# SNES_DRONE_PSU.net
KiCad netlist of a schematic drawn in Altium Designer
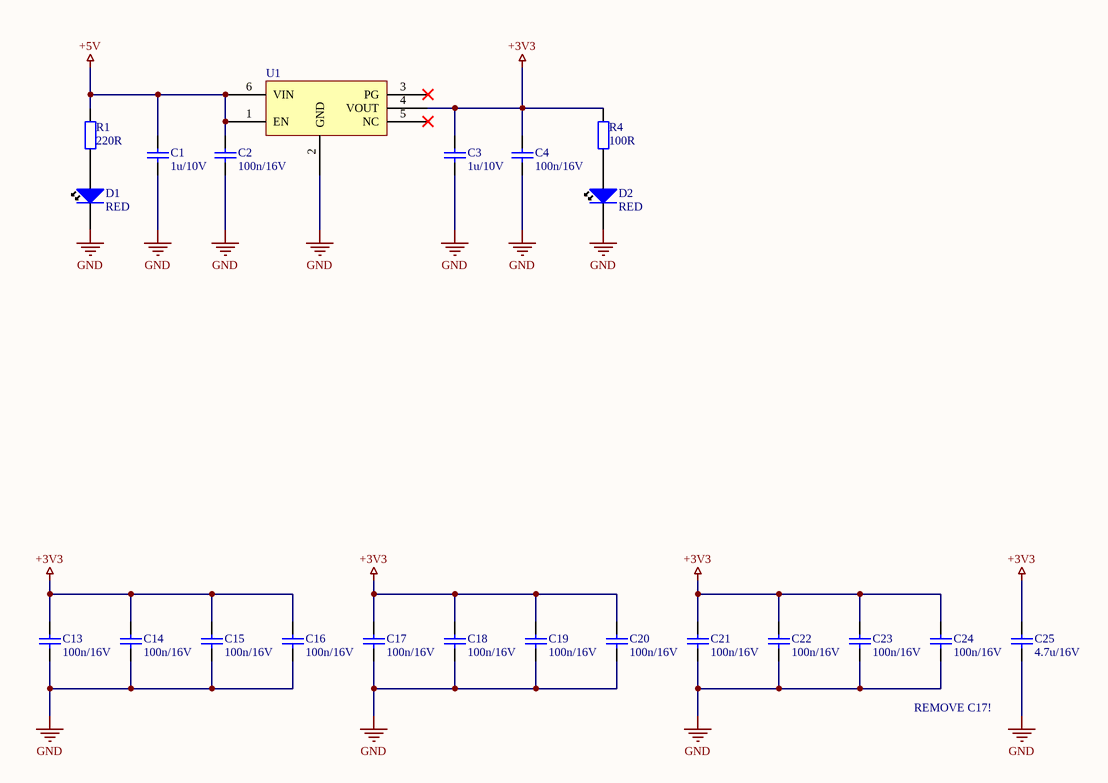
[diagram p0: SNES_DRONE_PSU.SchDoc]

(export (version "E")
  (design (tool "Eeschema 10.0.6"))
  (components
    (comp (ref "C1")
      (value "1u/10V")
      (footprint "0603_RES")
      (description "Keramikvielschichtkondensator, SMD, 1 µF, 10 V, 0603 [Metrisch 1608], ± 20%, X5R, WCAP-CSGP Series")
      (libsource (lib "My_Integrated_Library") (part "Cap_1u_0603"))
    )
    (comp (ref "C2")
      (value "100n/16V")
      (footprint "0402_RES")
      (description "Keramikvielschichtkondensator, SMD, 0.1 µF, 16 V, 0402 [Metrisch 1005], ± 10%, X5R, Baureihe MC")
      (libsource (lib "My_Integrated_Library") (part "Cap_100n_0402"))
    )
    (comp (ref "C3")
      (value "1u/10V")
      (footprint "0603_RES")
      (description "Keramikvielschichtkondensator, SMD, 1 µF, 10 V, 0603 [Metrisch 1608], ± 20%, X5R, WCAP-CSGP Series")
      (libsource (lib "My_Integrated_Library") (part "Cap_1u_0603"))
    )
    (comp (ref "C4")
      (value "100n/16V")
      (footprint "0402_RES")
      (description "Keramikvielschichtkondensator, SMD, 0.1 µF, 16 V, 0402 [Metrisch 1005], ± 10%, X5R, Baureihe MC")
      (libsource (lib "My_Integrated_Library") (part "Cap_100n_0402"))
    )
    (comp (ref "C13")
      (value "100n/16V")
      (footprint "0402_RES")
      (description "Keramikvielschichtkondensator, SMD, 0.1 µF, 16 V, 0402 [Metrisch 1005], ± 10%, X5R, Baureihe MC")
      (libsource (lib "My_Integrated_Library") (part "Cap_100n_0402"))
    )
    (comp (ref "C14")
      (value "100n/16V")
      (footprint "0402_RES")
      (description "Keramikvielschichtkondensator, SMD, 0.1 µF, 16 V, 0402 [Metrisch 1005], ± 10%, X5R, Baureihe MC")
      (libsource (lib "My_Integrated_Library") (part "Cap_100n_0402"))
    )
    (comp (ref "C15")
      (value "100n/16V")
      (footprint "0402_RES")
      (description "Keramikvielschichtkondensator, SMD, 0.1 µF, 16 V, 0402 [Metrisch 1005], ± 10%, X5R, Baureihe MC")
      (libsource (lib "My_Integrated_Library") (part "Cap_100n_0402"))
    )
    (comp (ref "C16")
      (value "100n/16V")
      (footprint "0402_RES")
      (description "Keramikvielschichtkondensator, SMD, 0.1 µF, 16 V, 0402 [Metrisch 1005], ± 10%, X5R, Baureihe MC")
      (libsource (lib "My_Integrated_Library") (part "Cap_100n_0402"))
    )
    (comp (ref "C17")
      (value "100n/16V")
      (footprint "0402_RES")
      (description "Keramikvielschichtkondensator, SMD, 0.1 µF, 16 V, 0402 [Metrisch 1005], ± 10%, X5R, Baureihe MC")
      (libsource (lib "My_Integrated_Library") (part "Cap_100n_0402"))
    )
    (comp (ref "C18")
      (value "100n/16V")
      (footprint "0402_RES")
      (description "Keramikvielschichtkondensator, SMD, 0.1 µF, 16 V, 0402 [Metrisch 1005], ± 10%, X5R, Baureihe MC")
      (libsource (lib "My_Integrated_Library") (part "Cap_100n_0402"))
    )
    (comp (ref "C19")
      (value "100n/16V")
      (footprint "0402_RES")
      (description "Keramikvielschichtkondensator, SMD, 0.1 µF, 16 V, 0402 [Metrisch 1005], ± 10%, X5R, Baureihe MC")
      (libsource (lib "My_Integrated_Library") (part "Cap_100n_0402"))
    )
    (comp (ref "C20")
      (value "100n/16V")
      (footprint "0402_RES")
      (description "Keramikvielschichtkondensator, SMD, 0.1 µF, 16 V, 0402 [Metrisch 1005], ± 10%, X5R, Baureihe MC")
      (libsource (lib "My_Integrated_Library") (part "Cap_100n_0402"))
    )
    (comp (ref "C21")
      (value "100n/16V")
      (footprint "0402_RES")
      (description "Keramikvielschichtkondensator, SMD, 0.1 µF, 16 V, 0402 [Metrisch 1005], ± 10%, X5R, Baureihe MC")
      (libsource (lib "My_Integrated_Library") (part "Cap_100n_0402"))
    )
    (comp (ref "C22")
      (value "100n/16V")
      (footprint "0402_RES")
      (description "Keramikvielschichtkondensator, SMD, 0.1 µF, 16 V, 0402 [Metrisch 1005], ± 10%, X5R, Baureihe MC")
      (libsource (lib "My_Integrated_Library") (part "Cap_100n_0402"))
    )
    (comp (ref "C23")
      (value "100n/16V")
      (footprint "0402_RES")
      (description "Keramikvielschichtkondensator, SMD, 0.1 µF, 16 V, 0402 [Metrisch 1005], ± 10%, X5R, Baureihe MC")
      (libsource (lib "My_Integrated_Library") (part "Cap_100n_0402"))
    )
    (comp (ref "C24")
      (value "100n/16V")
      (footprint "0402_RES")
      (description "Keramikvielschichtkondensator, SMD, 0.1 µF, 16 V, 0402 [Metrisch 1005], ± 10%, X5R, Baureihe MC")
      (libsource (lib "My_Integrated_Library") (part "Cap_100n_0402"))
    )
    (comp (ref "C25")
      (value "4.7u/16V")
      (footprint "0603_RES")
      (description "Keramikvielschichtkondensator, SMD, 4.7 µF, 16 V, 0603 [Metrisch 1608], ± 10%, X5R, Baureihe C")
      (libsource (lib "My_Integrated_Library") (part "Cap_4u7_0603"))
    )
    (comp (ref "D1")
      (value "RED")
      (footprint "0603_LED")
      (description "RED SMD 0603 LED 20mA 2V 0.04W")
      (fields (field (name "Comment") "RED LED"))
      (libsource (lib "My_Integrated_Library") (part "LED_RED_0603"))
    )
    (comp (ref "D2")
      (value "RED")
      (footprint "0603_LED")
      (description "RED SMD 0603 LED 20mA 2V 0.04W")
      (fields (field (name "Comment") "RED LED"))
      (libsource (lib "My_Integrated_Library") (part "LED_RED_0603"))
    )
    (comp (ref "R1")
      (value "220R")
      (footprint "0603_RES")
      (description "YAGEO 220Ohm 100mW ± 1%")
      (fields (field (name "Comment") "220Ohm 100mW"))
      (libsource (lib "My_Integrated_Library") (part "RES_0603_220_100mW"))
    )
    (comp (ref "R4")
      (value "100R")
      (footprint "0603_RES")
      (description "PANASONIC ELECTRONIC COMPONENTS 100Ohm 100mW ± 1%")
      (fields (field (name "Comment") "100Ohm 100mW"))
      (libsource (lib "My_Integrated_Library") (part "RES_0603_100_100mW"))
    )
    (comp (ref "U1")
      (value "3V3 LDO")
      (footprint "DFN6_3x3")
      (description "1.5V bis 5.5V, 200mV Dropout, 3.3Vout/500mAout, DFN-6")
      (libsource (lib "My_Integrated_Library") (part "IC_LD39050PU33R"))
    )
  )
  (nets
    (net (code "1") (name "+3V3") (class "Default")
      (node (ref "C13") (pin "2") (pinfunction "2_2") (pintype "passive"))
      (node (ref "C14") (pin "2") (pinfunction "2_2") (pintype "passive"))
      (node (ref "C15") (pin "2") (pinfunction "2_2") (pintype "passive"))
      (node (ref "C16") (pin "2") (pinfunction "2_2") (pintype "passive"))
      (node (ref "C17") (pin "2") (pinfunction "2_2") (pintype "passive"))
      (node (ref "C18") (pin "2") (pinfunction "2_2") (pintype "passive"))
      (node (ref "C19") (pin "2") (pinfunction "2_2") (pintype "passive"))
      (node (ref "C20") (pin "2") (pinfunction "2_2") (pintype "passive"))
      (node (ref "C21") (pin "2") (pinfunction "2_2") (pintype "passive"))
      (node (ref "C22") (pin "2") (pinfunction "2_2") (pintype "passive"))
      (node (ref "C23") (pin "2") (pinfunction "2_2") (pintype "passive"))
      (node (ref "C24") (pin "2") (pinfunction "2_2") (pintype "passive"))
      (node (ref "C25") (pin "2") (pinfunction "2_2") (pintype "passive"))
      (node (ref "C3") (pin "2") (pinfunction "2_2") (pintype "passive"))
      (node (ref "C4") (pin "2") (pinfunction "2_2") (pintype "passive"))
      (node (ref "R4") (pin "2") (pinfunction "2_2") (pintype "passive"))
      (node (ref "U1") (pin "4") (pinfunction "VOUT_4") (pintype "power_in"))
    )
    (net (code "2") (name "+5V") (class "Default")
      (node (ref "C1") (pin "2") (pinfunction "2_2") (pintype "passive"))
      (node (ref "C2") (pin "2") (pinfunction "2_2") (pintype "passive"))
      (node (ref "R1") (pin "2") (pinfunction "2_2") (pintype "passive"))
      (node (ref "U1") (pin "1") (pinfunction "EN_1") (pintype "passive"))
      (node (ref "U1") (pin "6") (pinfunction "VIN_6") (pintype "power_in"))
    )
    (net (code "3") (name "GND") (class "Default")
      (node (ref "C1") (pin "1") (pinfunction "1_1") (pintype "passive"))
      (node (ref "C13") (pin "1") (pinfunction "1_1") (pintype "passive"))
      (node (ref "C14") (pin "1") (pinfunction "1_1") (pintype "passive"))
      (node (ref "C15") (pin "1") (pinfunction "1_1") (pintype "passive"))
      (node (ref "C16") (pin "1") (pinfunction "1_1") (pintype "passive"))
      (node (ref "C17") (pin "1") (pinfunction "1_1") (pintype "passive"))
      (node (ref "C18") (pin "1") (pinfunction "1_1") (pintype "passive"))
      (node (ref "C19") (pin "1") (pinfunction "1_1") (pintype "passive"))
      (node (ref "C2") (pin "1") (pinfunction "1_1") (pintype "passive"))
      (node (ref "C20") (pin "1") (pinfunction "1_1") (pintype "passive"))
      (node (ref "C21") (pin "1") (pinfunction "1_1") (pintype "passive"))
      (node (ref "C22") (pin "1") (pinfunction "1_1") (pintype "passive"))
      (node (ref "C23") (pin "1") (pinfunction "1_1") (pintype "passive"))
      (node (ref "C24") (pin "1") (pinfunction "1_1") (pintype "passive"))
      (node (ref "C25") (pin "1") (pinfunction "1_1") (pintype "passive"))
      (node (ref "C3") (pin "1") (pinfunction "1_1") (pintype "passive"))
      (node (ref "C4") (pin "1") (pinfunction "1_1") (pintype "passive"))
      (node (ref "D1") (pin "2") (pinfunction "K_2") (pintype "passive"))
      (node (ref "D2") (pin "2") (pinfunction "K_2") (pintype "passive"))
      (node (ref "U1") (pin "2") (pinfunction "GND_2") (pintype "power_in"))
    )
    (net (code "4") (name "Net-(D1-A)") (class "Default")
      (node (ref "D1") (pin "1") (pinfunction "A_1") (pintype "passive"))
      (node (ref "R1") (pin "1") (pinfunction "1_1") (pintype "passive"))
    )
    (net (code "5") (name "Net-(D2-A)") (class "Default")
      (node (ref "D2") (pin "1") (pinfunction "A_1") (pintype "passive"))
      (node (ref "R4") (pin "1") (pinfunction "1_1") (pintype "passive"))
    )
    (net (code "6") (name "unconnected-(U1-NC-Pad5)") (class "Default")
      (node (ref "U1") (pin "5") (pinfunction "NC_5") (pintype "passive+no_connect"))
    )
    (net (code "7") (name "unconnected-(U1-PG-Pad3)") (class "Default")
      (node (ref "U1") (pin "3") (pinfunction "PG_3") (pintype "passive+no_connect"))
    )
  )
)
